# AtTiny_Board_schV3.net
KiCad netlist of a schematic drawn in EAGLE
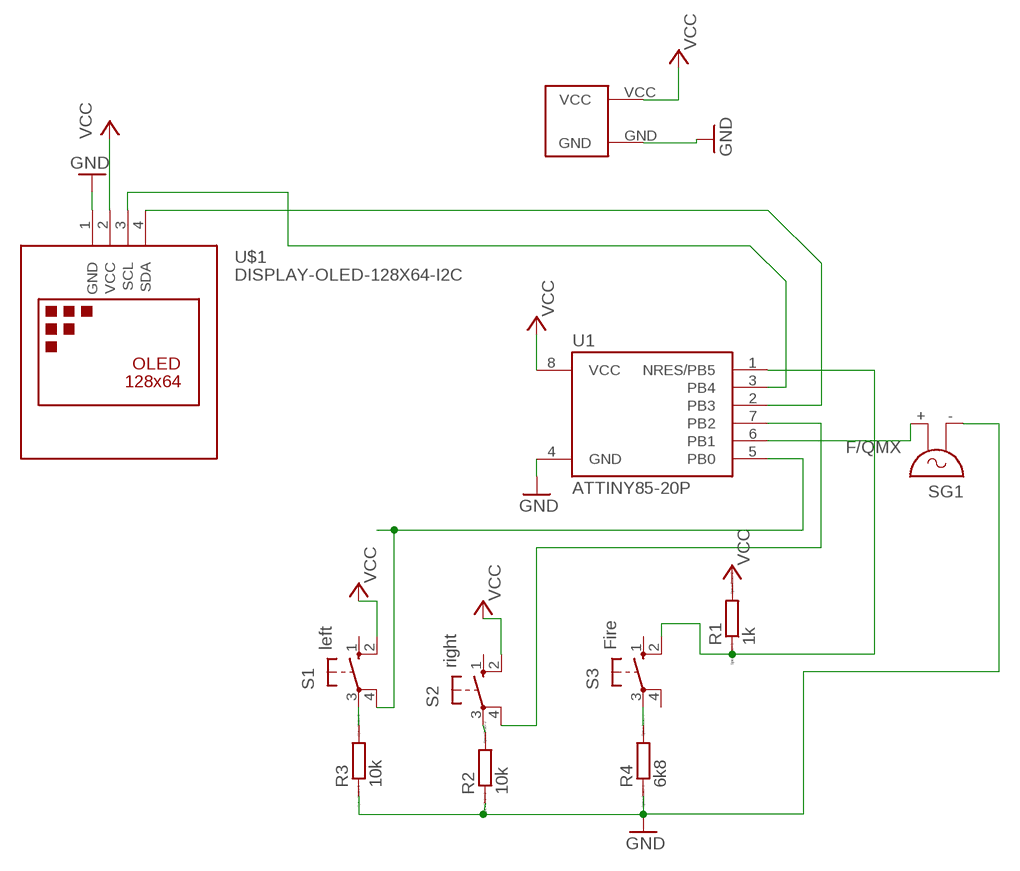
[diagram p0: schematic, sheet 1]

(export (version "E")
  (design (tool "Eeschema 10.0.6"))
  (components
    (comp (ref "R1")
      (value "1k")
      (footprint "eagle-import:0204_7")
      (libsource (lib "eagle-import") (part "R0204/7"))
    )
    (comp (ref "R2")
      (value "10k")
      (footprint "eagle-import:0204_7")
      (libsource (lib "eagle-import") (part "R0204/7"))
    )
    (comp (ref "R3")
      (value "10k")
      (footprint "eagle-import:0204_7")
      (libsource (lib "eagle-import") (part "R0204/7"))
    )
    (comp (ref "R4")
      (value "6k8")
      (footprint "eagle-import:0204_7")
      (libsource (lib "eagle-import") (part "R0204/7"))
    )
    (comp (ref "S1")
      (value "left")
      (footprint "eagle-import:B3F-10XX")
      (fields (field (name "MPN") "B3F-1000"))
      (libsource (lib "eagle-import") (part "10-XX"))
    )
    (comp (ref "S2")
      (value "right")
      (footprint "eagle-import:B3F-10XX")
      (fields (field (name "MPN") "B3F-1000"))
      (libsource (lib "eagle-import") (part "10-XX"))
    )
    (comp (ref "S3")
      (value "Fire")
      (footprint "eagle-import:B3F-10XX")
      (fields (field (name "MPN") "B3F-1000"))
      (libsource (lib "eagle-import") (part "10-XX"))
    )
    (comp (ref "SG1")
      (value "F/QMX")
      (footprint "eagle-import:F_QMX")
      (libsource (lib "eagle-import") (part "F/QMX"))
    )
    (comp (ref "U$1")
      (value "DISPLAY-OLED-128X64-I2C")
      (footprint "eagle-import:DISPLAY-OLED-128X64-I2C")
      (libsource (lib "eagle-import") (part "DISPLAY-OLED-128X64-I2C"))
    )
    (comp (ref "U$3")
      (value "CR2032_19MMDB")
      (footprint "eagle-import:CR2032-19MM")
      (libsource (lib "eagle-import") (part "CR2032_19MMDB"))
    )
    (comp (ref "U1")
      (value "ATTINY85-20P")
      (footprint "eagle-import:PDIP08_300MIL")
      (libsource (lib "eagle-import") (part "ATTINY85P-20"))
    )
  )
  (nets
    (net (code "1") (name "GND") (class "Default")
      (node (ref "R2") (pin "1") (pinfunction "1_1") (pintype "passive"))
      (node (ref "R3") (pin "1") (pinfunction "1_1") (pintype "passive"))
      (node (ref "R4") (pin "1") (pinfunction "1_1") (pintype "passive"))
      (node (ref "SG1") (pin "-") (pinfunction "1_-") (pintype "passive"))
      (node (ref "U$1") (pin "1") (pinfunction "GND_1") (pintype "power_in"))
      (node (ref "U$3") (pin "GND") (pinfunction "GND_GND") (pintype "bidirectional"))
      (node (ref "U1") (pin "4") (pinfunction "GND_4") (pintype "power_in"))
    )
    (net (code "2") (name "Net-(S1-P)") (class "Default")
      (node (ref "R3") (pin "2") (pinfunction "2_2") (pintype "passive"))
      (node (ref "S1") (pin "3") (pinfunction "P_3") (pintype "passive"))
    )
    (net (code "3") (name "Net-(S1-P1)") (class "Default")
      (node (ref "S1") (pin "4") (pinfunction "P1_4") (pintype "passive"))
      (node (ref "U1") (pin "5") (pinfunction "PB0_5") (pintype "bidirectional"))
    )
    (net (code "4") (name "Net-(S2-P)") (class "Default")
      (node (ref "R2") (pin "2") (pinfunction "2_2") (pintype "passive"))
      (node (ref "S2") (pin "3") (pinfunction "P_3") (pintype "passive"))
    )
    (net (code "5") (name "Net-(S2-P1)") (class "Default")
      (node (ref "S2") (pin "4") (pinfunction "P1_4") (pintype "passive"))
      (node (ref "U1") (pin "7") (pinfunction "PB2_7") (pintype "bidirectional"))
    )
    (net (code "6") (name "Net-(S3-P)") (class "Default")
      (node (ref "R4") (pin "2") (pinfunction "2_2") (pintype "passive"))
      (node (ref "S3") (pin "3") (pinfunction "P_3") (pintype "passive"))
    )
    (net (code "7") (name "Net-(S3-S1)") (class "Default")
      (node (ref "R1") (pin "1") (pinfunction "1_1") (pintype "passive"))
      (node (ref "S3") (pin "2") (pinfunction "S1_2") (pintype "passive"))
      (node (ref "U1") (pin "1") (pinfunction "NRES/PB5_1") (pintype "bidirectional"))
    )
    (net (code "8") (name "Net-(SG1-2)") (class "Default")
      (node (ref "SG1") (pin "+") (pinfunction "2_+") (pintype "passive"))
      (node (ref "U1") (pin "6") (pinfunction "PB1_6") (pintype "bidirectional"))
    )
    (net (code "9") (name "Net-(U$1-SCL)") (class "Default")
      (node (ref "U$1") (pin "3") (pinfunction "SCL_3") (pintype "bidirectional"))
      (node (ref "U1") (pin "3") (pinfunction "PB4_3") (pintype "bidirectional"))
    )
    (net (code "10") (name "Net-(U$1-SDA)") (class "Default")
      (node (ref "U$1") (pin "4") (pinfunction "SDA_4") (pintype "bidirectional"))
      (node (ref "U1") (pin "2") (pinfunction "PB3_2") (pintype "bidirectional"))
    )
    (net (code "11") (name "VCC") (class "Default")
      (node (ref "R1") (pin "2") (pinfunction "2_2") (pintype "passive"))
      (node (ref "S1") (pin "2") (pinfunction "S1_2") (pintype "passive"))
      (node (ref "S2") (pin "2") (pinfunction "S1_2") (pintype "passive"))
      (node (ref "U$1") (pin "2") (pinfunction "VCC_2") (pintype "power_in"))
      (node (ref "U$3") (pin "VCC") (pinfunction "VCC_VCC") (pintype "bidirectional"))
      (node (ref "U1") (pin "8") (pinfunction "VCC_8") (pintype "power_in"))
    )
    (net (code "12") (name "unconnected-(S1-S-Pad1)") (class "Default")
      (node (ref "S1") (pin "1") (pinfunction "S_1") (pintype "passive"))
    )
    (net (code "13") (name "unconnected-(S2-S-Pad1)") (class "Default")
      (node (ref "S2") (pin "1") (pinfunction "S_1") (pintype "passive"))
    )
    (net (code "14") (name "unconnected-(S3-P1-Pad4)") (class "Default")
      (node (ref "S3") (pin "4") (pinfunction "P1_4") (pintype "passive"))
    )
    (net (code "15") (name "unconnected-(S3-S-Pad1)") (class "Default")
      (node (ref "S3") (pin "1") (pinfunction "S_1") (pintype "passive"))
    )
  )
)
